# RST.net
KiCad netlist of a schematic drawn in Altium Designer
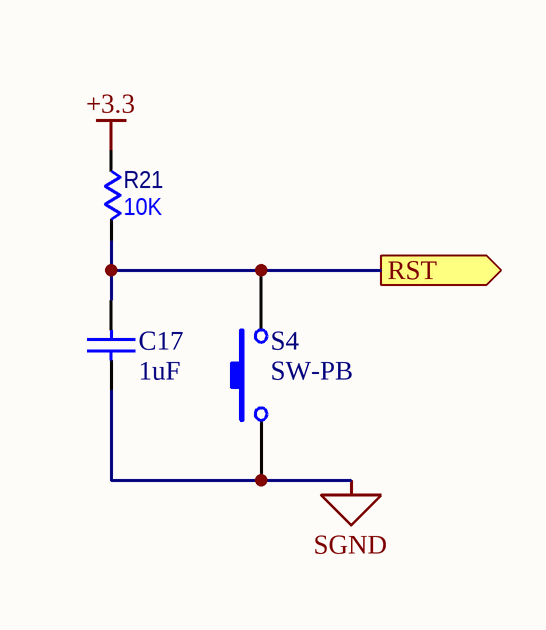
[diagram p0: RST.SchDoc]

(export (version "E")
  (design (tool "Eeschema 10.0.6"))
  (components
    (comp (ref "C17")
      (value "1uF")
      (footprint "0603")
      (description "无极性电容")
      (fields (field (name "Comment") "Cap") (field (name "PUBLISHER") "Altium Limited"))
      (libsource (lib "haoze") (part "Cap"))
    )
    (comp (ref "R21")
      (value "10K")
      (footprint "0603")
      (description "常规电阻")
      (fields (field (name "Comment") "Res"))
      (libsource (lib "haoze") (part "Res"))
    )
    (comp (ref "S4")
      (value "SW-PB")
      (footprint "SW_PB2_A1")
      (description "微动开关")
      (fields (field (name "PUBLISHER") "Altium Limited"))
      (libsource (lib "haoze") (part "SW-PB"))
    )
  )
  (nets
    (net (code "1") (name "+3.3") (class "Default")
      (node (ref "R21") (pin "1") (pinfunction "1_1") (pintype "passive"))
    )
    (net (code "2") (name "/RST") (class "Default")
      (node (ref "C17") (pin "2") (pinfunction "2_2") (pintype "passive"))
      (node (ref "R21") (pin "2") (pinfunction "2_2") (pintype "passive"))
      (node (ref "S4") (pin "2") (pinfunction "2_2") (pintype "passive"))
    )
    (net (code "3") (name "SGND") (class "Default")
      (node (ref "C17") (pin "1") (pinfunction "1_1") (pintype "passive"))
      (node (ref "S4") (pin "1") (pinfunction "1_1") (pintype "passive"))
    )
  )
)
